# Display.net
KiCad netlist of a schematic drawn in EAGLE
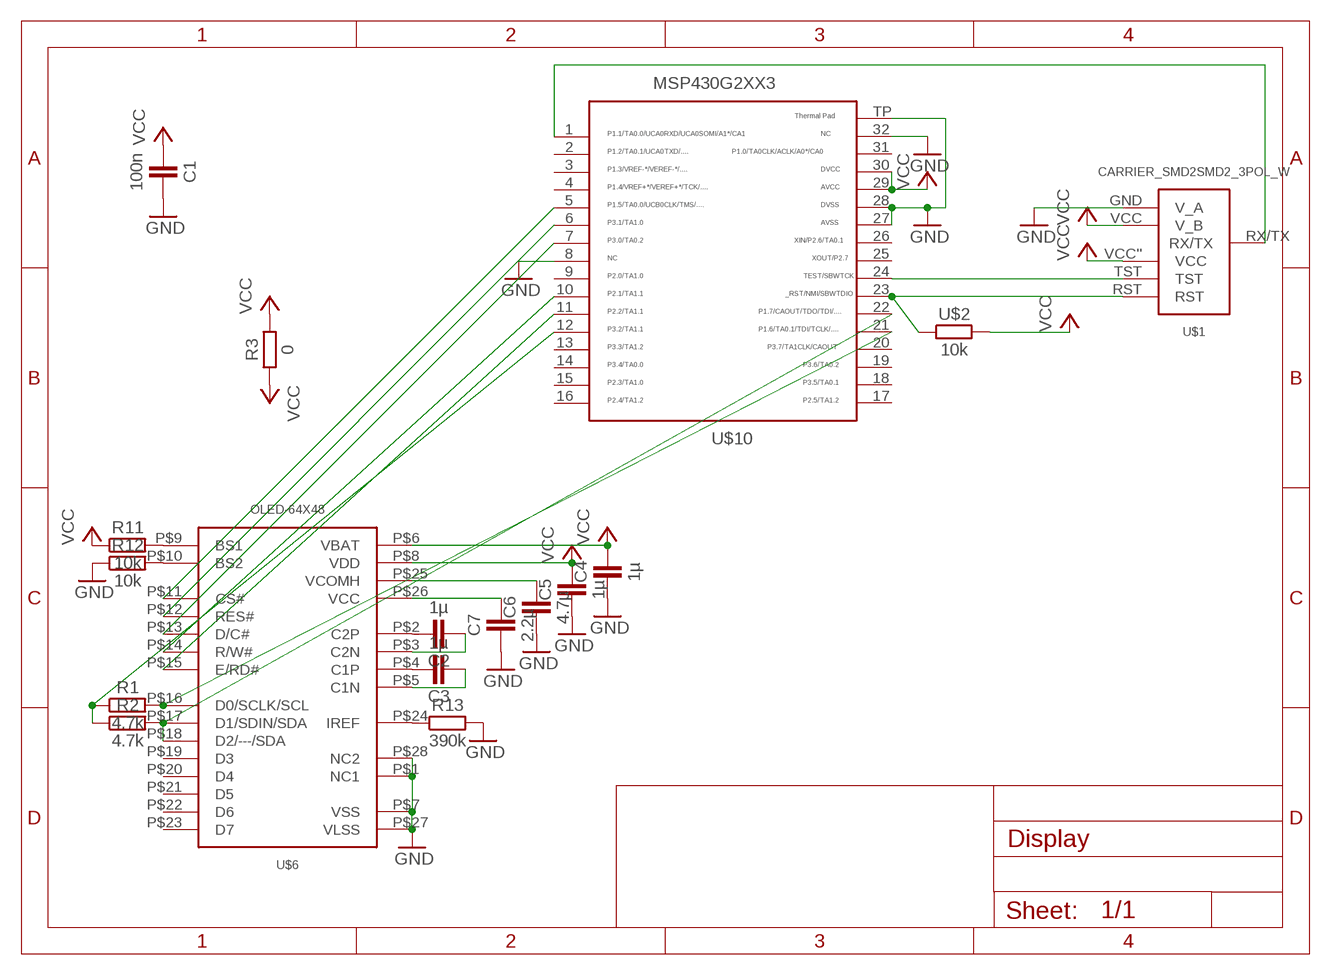
[diagram p0: schematic, sheet 1]

(export (version "E")
  (design (tool "Eeschema 10.0.6"))
  (components
    (comp (ref "C1")
      (value "100n")
      (footprint "eagle-import:603")
      (libsource (lib "eagle-import") (part "CAPACITOR"))
    )
    (comp (ref "C2")
      (value "1µ")
      (footprint "eagle-import:603")
      (libsource (lib "eagle-import") (part "CAPACITOR"))
    )
    (comp (ref "C3")
      (value "1µ")
      (footprint "eagle-import:603")
      (libsource (lib "eagle-import") (part "CAPACITOR"))
    )
    (comp (ref "C4")
      (value "1µ")
      (footprint "eagle-import:603")
      (libsource (lib "eagle-import") (part "CAPACITOR"))
    )
    (comp (ref "C5")
      (value "1µ")
      (footprint "eagle-import:603")
      (libsource (lib "eagle-import") (part "CAPACITOR"))
    )
    (comp (ref "C6")
      (value "4.7µ")
      (footprint "eagle-import:603")
      (libsource (lib "eagle-import") (part "CAPACITOR"))
    )
    (comp (ref "C7")
      (value "2.2µ")
      (footprint "eagle-import:603")
      (libsource (lib "eagle-import") (part "CAPACITOR"))
    )
    (comp (ref "R1")
      (value "4.7k")
      (footprint "eagle-import:603")
      (libsource (lib "eagle-import") (part "RESISTOR0603"))
    )
    (comp (ref "R2")
      (value "4.7k")
      (footprint "eagle-import:603")
      (libsource (lib "eagle-import") (part "RESISTOR0603"))
    )
    (comp (ref "R3")
      (value "0")
      (footprint "eagle-import:603")
      (libsource (lib "eagle-import") (part "RESISTOR0603"))
    )
    (comp (ref "R11")
      (value "10k")
      (footprint "eagle-import:603")
      (libsource (lib "eagle-import") (part "RESISTOR0603"))
    )
    (comp (ref "R12")
      (value "10k")
      (footprint "eagle-import:603")
      (libsource (lib "eagle-import") (part "RESISTOR0603"))
    )
    (comp (ref "R13")
      (value "390k")
      (footprint "eagle-import:603")
      (libsource (lib "eagle-import") (part "RESISTOR0603"))
    )
    (comp (ref "U$1")
      (value "CARRIER_SMD2SMD2_3POL_W")
      (footprint "eagle-import:CARRIER_SMD2_WIDE_3POL")
      (libsource (lib "eagle-import") (part "CARRIER_SMD2SMD2_3POL_W"))
    )
    (comp (ref "U$2")
      (value "10k")
      (footprint "eagle-import:603")
      (libsource (lib "eagle-import") (part "RESISTOR0603"))
    )
    (comp (ref "U$6")
      (value "OLED-64X48")
      (footprint "eagle-import:OLED_DISPLAY")
      (libsource (lib "eagle-import") (part "OLED-64X48"))
    )
    (comp (ref "U$10")
      (value "MSP430G2553")
      (footprint "eagle-import:QFN32")
      (libsource (lib "eagle-import") (part "MSP430G2553"))
    )
  )
  (nets
    (net (code "1") (name "GND") (class "Default")
      (node (ref "C1") (pin "2") (pinfunction "2_2") (pintype "passive"))
      (node (ref "C4") (pin "1") (pinfunction "1_1") (pintype "passive"))
      (node (ref "C5") (pin "1") (pinfunction "1_1") (pintype "passive"))
      (node (ref "C6") (pin "1") (pinfunction "1_1") (pintype "passive"))
      (node (ref "C7") (pin "1") (pinfunction "1_1") (pintype "passive"))
      (node (ref "R12") (pin "1") (pinfunction "1_1") (pintype "passive"))
      (node (ref "R13") (pin "2") (pinfunction "2_2") (pintype "passive"))
      (node (ref "U$1") (pin "GND") (pinfunction "V_A_GND") (pintype "bidirectional"))
      (node (ref "U$10") (pin "27") (pinfunction "27_27") (pintype "bidirectional"))
      (node (ref "U$10") (pin "28") (pinfunction "28_28") (pintype "bidirectional"))
      (node (ref "U$10") (pin "32") (pinfunction "32_32") (pintype "bidirectional"))
      (node (ref "U$10") (pin "8") (pinfunction "8_8") (pintype "bidirectional"))
      (node (ref "U$10") (pin "TP") (pinfunction "TP_TP") (pintype "bidirectional"))
      (node (ref "U$6") (pin "P$1") (pinfunction "NC1_P$1") (pintype "bidirectional"))
      (node (ref "U$6") (pin "P$27") (pinfunction "VLSS_P$27") (pintype "bidirectional"))
      (node (ref "U$6") (pin "P$28") (pinfunction "NC2_P$28") (pintype "bidirectional"))
      (node (ref "U$6") (pin "P$7") (pinfunction "VSS_P$7") (pintype "bidirectional"))
    )
    (net (code "2") (name "Net-(R1-Pad1)") (class "Default")
      (node (ref "R1") (pin "1") (pinfunction "1_1") (pintype "passive"))
      (node (ref "R2") (pin "1") (pinfunction "1_1") (pintype "passive"))
      (node (ref "U$10") (pin "12") (pinfunction "12_12") (pintype "bidirectional"))
    )
    (net (code "3") (name "Net-(U$1-PadRST)") (class "Default")
      (node (ref "U$1") (pin "RST") (pinfunction "RST_RST") (pintype "bidirectional"))
      (node (ref "U$10") (pin "23") (pinfunction "23_23") (pintype "bidirectional"))
      (node (ref "U$2") (pin "1") (pinfunction "1_1") (pintype "passive"))
    )
    (net (code "4") (name "Net-(U$1-PadRX{slash}TX)") (class "Default")
      (node (ref "U$1") (pin "RX/TX") (pinfunction "RX/TX_RX/TX") (pintype "bidirectional"))
      (node (ref "U$10") (pin "1") (pinfunction "1_1") (pintype "bidirectional"))
    )
    (net (code "5") (name "Net-(U$1-PadTST)") (class "Default")
      (node (ref "U$1") (pin "TST") (pinfunction "TST_TST") (pintype "bidirectional"))
      (node (ref "U$10") (pin "24") (pinfunction "24_24") (pintype "bidirectional"))
    )
    (net (code "6") (name "Net-(U$6-BS1)") (class "Default")
      (node (ref "R11") (pin "2") (pinfunction "2_2") (pintype "passive"))
      (node (ref "U$6") (pin "P$9") (pinfunction "BS1_P$9") (pintype "bidirectional"))
    )
    (net (code "7") (name "Net-(U$6-BS2)") (class "Default")
      (node (ref "R12") (pin "2") (pinfunction "2_2") (pintype "passive"))
      (node (ref "U$6") (pin "P$10") (pinfunction "BS2_P$10") (pintype "bidirectional"))
    )
    (net (code "8") (name "Net-(U$6-C1N)") (class "Default")
      (node (ref "C3") (pin "1") (pinfunction "1_1") (pintype "passive"))
      (node (ref "U$6") (pin "P$5") (pinfunction "C1N_P$5") (pintype "bidirectional"))
    )
    (net (code "9") (name "Net-(U$6-C1P)") (class "Default")
      (node (ref "C3") (pin "2") (pinfunction "2_2") (pintype "passive"))
      (node (ref "U$6") (pin "P$4") (pinfunction "C1P_P$4") (pintype "bidirectional"))
    )
    (net (code "10") (name "Net-(U$6-C2N)") (class "Default")
      (node (ref "C2") (pin "1") (pinfunction "1_1") (pintype "passive"))
      (node (ref "U$6") (pin "P$3") (pinfunction "C2N_P$3") (pintype "bidirectional"))
    )
    (net (code "11") (name "Net-(U$6-C2P)") (class "Default")
      (node (ref "C2") (pin "2") (pinfunction "2_2") (pintype "passive"))
      (node (ref "U$6") (pin "P$2") (pinfunction "C2P_P$2") (pintype "bidirectional"))
    )
    (net (code "12") (name "Net-(U$6-CS#)") (class "Default")
      (node (ref "U$10") (pin "5") (pinfunction "5_5") (pintype "bidirectional"))
      (node (ref "U$6") (pin "P$11") (pinfunction "CS#_P$11") (pintype "bidirectional"))
    )
    (net (code "13") (name "Net-(U$6-D0{slash}SCLK{slash}SCL)") (class "Default")
      (node (ref "R1") (pin "2") (pinfunction "2_2") (pintype "passive"))
      (node (ref "U$10") (pin "21") (pinfunction "21_21") (pintype "bidirectional"))
      (node (ref "U$6") (pin "P$16") (pinfunction "D0/SCLK/SCL_P$16") (pintype "bidirectional"))
    )
    (net (code "14") (name "Net-(U$6-D1{slash}SDIN{slash}SDA)") (class "Default")
      (node (ref "R2") (pin "2") (pinfunction "2_2") (pintype "passive"))
      (node (ref "U$10") (pin "22") (pinfunction "22_22") (pintype "bidirectional"))
      (node (ref "U$6") (pin "P$17") (pinfunction "D1/SDIN/SDA_P$17") (pintype "bidirectional"))
      (node (ref "U$6") (pin "P$18") (pinfunction "D2/---/SDA_P$18") (pintype "bidirectional"))
    )
    (net (code "15") (name "Net-(U$6-D{slash}C#)") (class "Default")
      (node (ref "U$10") (pin "7") (pinfunction "7_7") (pintype "bidirectional"))
      (node (ref "U$6") (pin "P$13") (pinfunction "D/C#_P$13") (pintype "bidirectional"))
    )
    (net (code "16") (name "Net-(U$6-E{slash}RD#)") (class "Default")
      (node (ref "U$10") (pin "11") (pinfunction "11_11") (pintype "bidirectional"))
      (node (ref "U$6") (pin "P$15") (pinfunction "E/RD#_P$15") (pintype "bidirectional"))
    )
    (net (code "17") (name "Net-(U$6-IREF)") (class "Default")
      (node (ref "R13") (pin "1") (pinfunction "1_1") (pintype "passive"))
      (node (ref "U$6") (pin "P$24") (pinfunction "IREF_P$24") (pintype "bidirectional"))
    )
    (net (code "18") (name "Net-(U$6-RES#)") (class "Default")
      (node (ref "U$10") (pin "6") (pinfunction "6_6") (pintype "bidirectional"))
      (node (ref "U$6") (pin "P$12") (pinfunction "RES#_P$12") (pintype "bidirectional"))
    )
    (net (code "19") (name "Net-(U$6-R{slash}W#)") (class "Default")
      (node (ref "U$10") (pin "10") (pinfunction "10_10") (pintype "bidirectional"))
      (node (ref "U$6") (pin "P$14") (pinfunction "R/W#_P$14") (pintype "bidirectional"))
    )
    (net (code "20") (name "Net-(U$6-VCC)") (class "Default")
      (node (ref "C7") (pin "2") (pinfunction "2_2") (pintype "passive"))
      (node (ref "U$6") (pin "P$26") (pinfunction "VCC_P$26") (pintype "bidirectional"))
    )
    (net (code "21") (name "Net-(U$6-VCOMH)") (class "Default")
      (node (ref "C6") (pin "2") (pinfunction "2_2") (pintype "passive"))
      (node (ref "U$6") (pin "P$25") (pinfunction "VCOMH_P$25") (pintype "bidirectional"))
    )
    (net (code "22") (name "VCC") (class "Default")
      (node (ref "C1") (pin "1") (pinfunction "1_1") (pintype "passive"))
      (node (ref "C4") (pin "2") (pinfunction "2_2") (pintype "passive"))
      (node (ref "C5") (pin "2") (pinfunction "2_2") (pintype "passive"))
      (node (ref "R11") (pin "1") (pinfunction "1_1") (pintype "passive"))
      (node (ref "R3") (pin "1") (pinfunction "1_1") (pintype "passive"))
      (node (ref "R3") (pin "2") (pinfunction "2_2") (pintype "passive"))
      (node (ref "U$1") (pin "VCC") (pinfunction "V_B_VCC") (pintype "bidirectional"))
      (node (ref "U$1") (pin "VCC''") (pinfunction "VCC_VCC''") (pintype "bidirectional"))
      (node (ref "U$10") (pin "29") (pinfunction "29_29") (pintype "bidirectional"))
      (node (ref "U$10") (pin "30") (pinfunction "30_30") (pintype "bidirectional"))
      (node (ref "U$2") (pin "2") (pinfunction "2_2") (pintype "passive"))
      (node (ref "U$6") (pin "P$6") (pinfunction "VBAT_P$6") (pintype "bidirectional"))
      (node (ref "U$6") (pin "P$8") (pinfunction "VDD_P$8") (pintype "bidirectional"))
    )
    (net (code "23") (name "unconnected-(U$6-D3-PadP$19)") (class "Default")
      (node (ref "U$6") (pin "P$19") (pinfunction "D3_P$19") (pintype "bidirectional"))
    )
    (net (code "24") (name "unconnected-(U$6-D4-PadP$20)") (class "Default")
      (node (ref "U$6") (pin "P$20") (pinfunction "D4_P$20") (pintype "bidirectional"))
    )
    (net (code "25") (name "unconnected-(U$6-D5-PadP$21)") (class "Default")
      (node (ref "U$6") (pin "P$21") (pinfunction "D5_P$21") (pintype "bidirectional"))
    )
    (net (code "26") (name "unconnected-(U$6-D6-PadP$22)") (class "Default")
      (node (ref "U$6") (pin "P$22") (pinfunction "D6_P$22") (pintype "bidirectional"))
    )
    (net (code "27") (name "unconnected-(U$6-D7-PadP$23)") (class "Default")
      (node (ref "U$6") (pin "P$23") (pinfunction "D7_P$23") (pintype "bidirectional"))
    )
    (net (code "28") (name "unconnected-(U$10-Pad2)") (class "Default")
      (node (ref "U$10") (pin "2") (pinfunction "2_2") (pintype "bidirectional"))
    )
    (net (code "29") (name "unconnected-(U$10-Pad3)") (class "Default")
      (node (ref "U$10") (pin "3") (pinfunction "3_3") (pintype "bidirectional"))
    )
    (net (code "30") (name "unconnected-(U$10-Pad4)") (class "Default")
      (node (ref "U$10") (pin "4") (pinfunction "4_4") (pintype "bidirectional"))
    )
    (net (code "31") (name "unconnected-(U$10-Pad9)") (class "Default")
      (node (ref "U$10") (pin "9") (pinfunction "9_9") (pintype "bidirectional"))
    )
    (net (code "32") (name "unconnected-(U$10-Pad13)") (class "Default")
      (node (ref "U$10") (pin "13") (pinfunction "13_13") (pintype "bidirectional"))
    )
    (net (code "33") (name "unconnected-(U$10-Pad14)") (class "Default")
      (node (ref "U$10") (pin "14") (pinfunction "14_14") (pintype "bidirectional"))
    )
    (net (code "34") (name "unconnected-(U$10-Pad15)") (class "Default")
      (node (ref "U$10") (pin "15") (pinfunction "15_15") (pintype "bidirectional"))
    )
    (net (code "35") (name "unconnected-(U$10-Pad16)") (class "Default")
      (node (ref "U$10") (pin "16") (pinfunction "16_16") (pintype "bidirectional"))
    )
    (net (code "36") (name "unconnected-(U$10-Pad17)") (class "Default")
      (node (ref "U$10") (pin "17") (pinfunction "17_17") (pintype "bidirectional"))
    )
    (net (code "37") (name "unconnected-(U$10-Pad18)") (class "Default")
      (node (ref "U$10") (pin "18") (pinfunction "18_18") (pintype "bidirectional"))
    )
    (net (code "38") (name "unconnected-(U$10-Pad19)") (class "Default")
      (node (ref "U$10") (pin "19") (pinfunction "19_19") (pintype "bidirectional"))
    )
    (net (code "39") (name "unconnected-(U$10-Pad20)") (class "Default")
      (node (ref "U$10") (pin "20") (pinfunction "20_20") (pintype "bidirectional"))
    )
    (net (code "40") (name "unconnected-(U$10-Pad25)") (class "Default")
      (node (ref "U$10") (pin "25") (pinfunction "25_25") (pintype "bidirectional"))
    )
    (net (code "41") (name "unconnected-(U$10-Pad26)") (class "Default")
      (node (ref "U$10") (pin "26") (pinfunction "26_26") (pintype "bidirectional"))
    )
    (net (code "42") (name "unconnected-(U$10-Pad31)") (class "Default")
      (node (ref "U$10") (pin "31") (pinfunction "31_31") (pintype "bidirectional"))
    )
  )
)
